# Motorbike_monitoring_and_Alarm.net
KiCad netlist of a schematic drawn in EAGLE
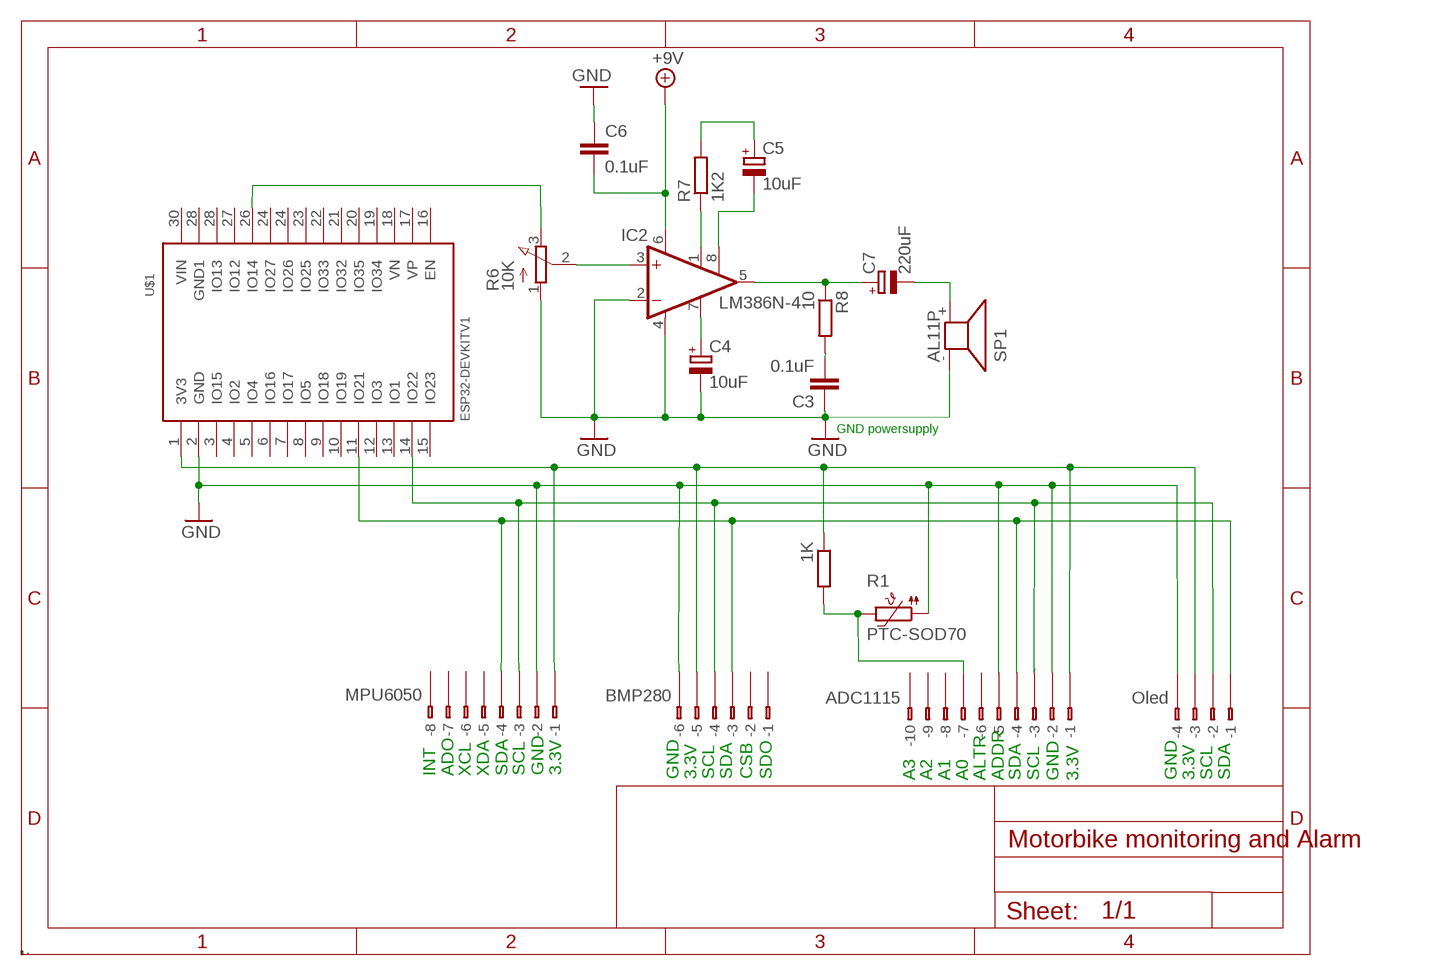
[diagram p0: schematic, sheet 1]

(export (version "E")
  (design (tool "Eeschema 10.0.6"))
  (components
    (comp (ref "ADC1115")
      (value "233-110")
      (footprint "eagle-import:233-110")
      (libsource (lib "eagle-import") (part "233-110"))
    )
    (comp (ref "C3")
      (value "0.1uF")
      (footprint "eagle-import:C050-024X044")
      (libsource (lib "eagle-import") (part "C-EU050-024X044"))
    )
    (comp (ref "C4")
      (value "10uF")
      (footprint "eagle-import:E1,8-4")
      (libsource (lib "eagle-import") (part "CPOL-EUE1.8-4"))
    )
    (comp (ref "C5")
      (value "10uF")
      (footprint "eagle-import:E1,8-4")
      (libsource (lib "eagle-import") (part "CPOL-EUE1.8-4"))
    )
    (comp (ref "C6")
      (value "0.1uF")
      (footprint "eagle-import:C050-024X044")
      (libsource (lib "eagle-import") (part "C-EU050-024X044"))
    )
    (comp (ref "C7")
      (value "220uF")
      (footprint "eagle-import:E1,8-4")
      (libsource (lib "eagle-import") (part "CPOL-EUE1.8-4"))
    )
    (comp (ref "IC2")
      (value "LM386N-4")
      (footprint "eagle-import:DIL08")
      (libsource (lib "eagle-import") (part "LM386?-N4"))
    )
    (comp (ref "MPU6050")
      (value "233-108")
      (footprint "eagle-import:233-108")
      (libsource (lib "eagle-import") (part "233-108"))
    )
    (comp (ref "R1")
      (value "PTC-SOD70")
      (footprint "eagle-import:SOD70")
      (libsource (lib "eagle-import") (part "PTC-SOD70"))
    )
    (comp (ref "R2")
      (value "1K")
      (footprint "eagle-import:0207_7")
      (libsource (lib "eagle-import") (part "R-EU_0207/7"))
    )
    (comp (ref "R6")
      (value "10K")
      (footprint "eagle-import:3RP_1610N")
      (libsource (lib "eagle-import") (part "3RP/1610N"))
    )
    (comp (ref "R7")
      (value "1K2")
      (footprint "eagle-import:0207_7")
      (libsource (lib "eagle-import") (part "R-EU_0207/7"))
    )
    (comp (ref "R8")
      (value "10")
      (footprint "eagle-import:0207_7")
      (libsource (lib "eagle-import") (part "R-EU_0207/7"))
    )
    (comp (ref "SP1")
      (value "AL11P")
      (footprint "eagle-import:AL11P")
      (libsource (lib "eagle-import") (part "AL11P"))
    )
    (comp (ref "U$1")
      (value "ESP32DEVKITV1")
      (footprint "eagle-import:ESP32-DEVKITV1")
      (libsource (lib "eagle-import") (part "ESP32DEVKITV1"))
    )
    (comp (ref "X1")
      (value "Oled")
      (footprint "eagle-import:233-104")
      (fields (field (name "MPN") "233-104"))
      (libsource (lib "eagle-import") (part "233-104"))
    )
    (comp (ref "X5")
      (value "BMP280")
      (footprint "eagle-import:233-106")
      (fields (field (name "MPN") "233-106"))
      (libsource (lib "eagle-import") (part "233-106"))
    )
  )
  (nets
    (net (code "1") (name "+9V") (class "Default")
      (node (ref "C6") (pin "2") (pinfunction "2_2") (pintype "passive"))
      (node (ref "IC2") (pin "6") (pinfunction "VS_6") (pintype "power_in"))
    )
    (net (code "2") (name "GND") (class "Default")
      (node (ref "ADC1115") (pin "B2") (pinfunction "B-2_B2") (pintype "passive"))
      (node (ref "MPU6050") (pin "B2") (pinfunction "B-2_B2") (pintype "passive"))
      (node (ref "U$1") (pin "2") (pinfunction "GND_2") (pintype "bidirectional"))
      (node (ref "X1") (pin "B4") (pinfunction "B-4_B4") (pintype "passive"))
      (node (ref "X5") (pin "B6") (pinfunction "B-6_B6") (pintype "passive"))
    )
    (net (code "3") (name "Net-(ADC1115-B-1)") (class "Default")
      (node (ref "ADC1115") (pin "B1") (pinfunction "B-1_B1") (pintype "passive"))
      (node (ref "MPU6050") (pin "B1") (pinfunction "B-1_B1") (pintype "passive"))
      (node (ref "R2") (pin "1") (pinfunction "1_1") (pintype "passive"))
      (node (ref "U$1") (pin "1") (pinfunction "3V3_1") (pintype "bidirectional"))
      (node (ref "X1") (pin "B3") (pinfunction "B-3_B3") (pintype "passive"))
      (node (ref "X5") (pin "B5") (pinfunction "B-5_B5") (pintype "passive"))
    )
    (net (code "4") (name "Net-(ADC1115-B-3)") (class "Default")
      (node (ref "ADC1115") (pin "B3") (pinfunction "B-3_B3") (pintype "passive"))
      (node (ref "MPU6050") (pin "B3") (pinfunction "B-3_B3") (pintype "passive"))
      (node (ref "U$1") (pin "14") (pinfunction "IO22_14") (pintype "bidirectional"))
      (node (ref "X1") (pin "B2") (pinfunction "B-2_B2") (pintype "passive"))
      (node (ref "X5") (pin "B4") (pinfunction "B-4_B4") (pintype "passive"))
    )
    (net (code "5") (name "Net-(ADC1115-B-4)") (class "Default")
      (node (ref "ADC1115") (pin "B4") (pinfunction "B-4_B4") (pintype "passive"))
      (node (ref "MPU6050") (pin "B4") (pinfunction "B-4_B4") (pintype "passive"))
      (node (ref "U$1") (pin "11") (pinfunction "IO21_11") (pintype "bidirectional"))
      (node (ref "X1") (pin "B1") (pinfunction "B-1_B1") (pintype "passive"))
      (node (ref "X5") (pin "B3") (pinfunction "B-3_B3") (pintype "passive"))
    )
    (net (code "6") (name "Net-(ADC1115-B-7)") (class "Default")
      (node (ref "ADC1115") (pin "B7") (pinfunction "B-7_B7") (pintype "passive"))
      (node (ref "R1") (pin "2") (pinfunction "2_2") (pintype "passive"))
      (node (ref "R2") (pin "2") (pinfunction "2_2") (pintype "passive"))
    )
    (net (code "7") (name "Net-(C3-Pad2)") (class "Default")
      (node (ref "C3") (pin "2") (pinfunction "2_2") (pintype "passive"))
      (node (ref "R8") (pin "2") (pinfunction "2_2") (pintype "passive"))
    )
    (net (code "8") (name "Net-(C5-Pad+)") (class "Default")
      (node (ref "C5") (pin "+") (pinfunction "+_+") (pintype "passive"))
      (node (ref "R7") (pin "2") (pinfunction "2_2") (pintype "passive"))
    )
    (net (code "9") (name "Net-(C5-Pad-)") (class "Default")
      (node (ref "C5") (pin "-") (pinfunction "-_-") (pintype "passive"))
      (node (ref "IC2") (pin "8") (pinfunction "GAIN_8") (pintype "passive"))
    )
    (net (code "10") (name "Net-(IC2-+IN)") (class "Default")
      (node (ref "IC2") (pin "3") (pinfunction "+IN_3") (pintype "input"))
      (node (ref "R6") (pin "2") (pinfunction "S_2") (pintype "passive"))
    )
    (net (code "11") (name "Net-(IC2--IN)") (class "Default")
      (node (ref "C3") (pin "1") (pinfunction "1_1") (pintype "passive"))
      (node (ref "C4") (pin "-") (pinfunction "-_-") (pintype "passive"))
      (node (ref "IC2") (pin "2") (pinfunction "-IN_2") (pintype "input"))
      (node (ref "IC2") (pin "4") (pinfunction "GND_4") (pintype "power_in"))
      (node (ref "R6") (pin "1") (pinfunction "A_1") (pintype "passive"))
      (node (ref "SP1") (pin "-") (pinfunction "1_-") (pintype "passive"))
    )
    (net (code "12") (name "Net-(IC2-BYPASS)") (class "Default")
      (node (ref "C4") (pin "+") (pinfunction "+_+") (pintype "passive"))
      (node (ref "IC2") (pin "7") (pinfunction "BYPASS_7") (pintype "passive"))
    )
    (net (code "13") (name "Net-(IC2-GAIN-Pad1)") (class "Default")
      (node (ref "IC2") (pin "1") (pinfunction "GAIN_1") (pintype "passive"))
      (node (ref "R7") (pin "1") (pinfunction "1_1") (pintype "passive"))
    )
    (net (code "14") (name "Net-(IC2-OUT)") (class "Default")
      (node (ref "C7") (pin "+") (pinfunction "+_+") (pintype "passive"))
      (node (ref "IC2") (pin "5") (pinfunction "OUT_5") (pintype "output"))
      (node (ref "R8") (pin "1") (pinfunction "1_1") (pintype "passive"))
    )
    (net (code "15") (name "Net-(R6-E)") (class "Default")
      (node (ref "R6") (pin "3") (pinfunction "E_3") (pintype "passive"))
      (node (ref "U$1") (pin "26") (pinfunction "IO14_26") (pintype "bidirectional"))
    )
    (net (code "16") (name "Net-(SP1-2)") (class "Default")
      (node (ref "C7") (pin "-") (pinfunction "-_-") (pintype "passive"))
      (node (ref "SP1") (pin "+") (pinfunction "2_+") (pintype "passive"))
    )
    (net (code "17") (name "unconnected-(ADC1115--1-PadA1)") (class "Default")
      (node (ref "ADC1115") (pin "A1") (pinfunction "-1_A1") (pintype "passive"))
    )
    (net (code "18") (name "unconnected-(ADC1115--2-PadA2)") (class "Default")
      (node (ref "ADC1115") (pin "A2") (pinfunction "-2_A2") (pintype "passive"))
    )
    (net (code "19") (name "unconnected-(ADC1115--3-PadA3)") (class "Default")
      (node (ref "ADC1115") (pin "A3") (pinfunction "-3_A3") (pintype "passive"))
    )
    (net (code "20") (name "unconnected-(ADC1115--4-PadA4)") (class "Default")
      (node (ref "ADC1115") (pin "A4") (pinfunction "-4_A4") (pintype "passive"))
    )
    (net (code "21") (name "unconnected-(ADC1115--5-PadA5)") (class "Default")
      (node (ref "ADC1115") (pin "A5") (pinfunction "-5_A5") (pintype "passive"))
    )
    (net (code "22") (name "unconnected-(ADC1115--6-PadA6)") (class "Default")
      (node (ref "ADC1115") (pin "A6") (pinfunction "-6_A6") (pintype "passive"))
    )
    (net (code "23") (name "unconnected-(ADC1115--7-PadA7)") (class "Default")
      (node (ref "ADC1115") (pin "A7") (pinfunction "-7_A7") (pintype "passive"))
    )
    (net (code "24") (name "unconnected-(ADC1115--8-PadA8)") (class "Default")
      (node (ref "ADC1115") (pin "A8") (pinfunction "-8_A8") (pintype "passive"))
    )
    (net (code "25") (name "unconnected-(ADC1115--9-PadA9)") (class "Default")
      (node (ref "ADC1115") (pin "A9") (pinfunction "-9_A9") (pintype "passive"))
    )
    (net (code "26") (name "unconnected-(ADC1115--10-PadA10)") (class "Default")
      (node (ref "ADC1115") (pin "A10") (pinfunction "-10_A10") (pintype "passive"))
    )
    (net (code "27") (name "unconnected-(ADC1115-B-5-PadB5)") (class "Default")
      (node (ref "ADC1115") (pin "B5") (pinfunction "B-5_B5") (pintype "passive"))
    )
    (net (code "28") (name "unconnected-(ADC1115-B-6-PadB6)") (class "Default")
      (node (ref "ADC1115") (pin "B6") (pinfunction "B-6_B6") (pintype "passive"))
    )
    (net (code "29") (name "unconnected-(ADC1115-B-8-PadB8)") (class "Default")
      (node (ref "ADC1115") (pin "B8") (pinfunction "B-8_B8") (pintype "passive"))
    )
    (net (code "30") (name "unconnected-(ADC1115-B-9-PadB9)") (class "Default")
      (node (ref "ADC1115") (pin "B9") (pinfunction "B-9_B9") (pintype "passive"))
    )
    (net (code "31") (name "unconnected-(ADC1115-B-10-PadB10)") (class "Default")
      (node (ref "ADC1115") (pin "B10") (pinfunction "B-10_B10") (pintype "passive"))
    )
    (net (code "32") (name "unconnected-(C6-Pad1)") (class "Default")
      (node (ref "C6") (pin "1") (pinfunction "1_1") (pintype "passive"))
    )
    (net (code "33") (name "unconnected-(MPU6050--1-PadA1)") (class "Default")
      (node (ref "MPU6050") (pin "A1") (pinfunction "-1_A1") (pintype "passive"))
    )
    (net (code "34") (name "unconnected-(MPU6050--2-PadA2)") (class "Default")
      (node (ref "MPU6050") (pin "A2") (pinfunction "-2_A2") (pintype "passive"))
    )
    (net (code "35") (name "unconnected-(MPU6050--3-PadA3)") (class "Default")
      (node (ref "MPU6050") (pin "A3") (pinfunction "-3_A3") (pintype "passive"))
    )
    (net (code "36") (name "unconnected-(MPU6050--4-PadA4)") (class "Default")
      (node (ref "MPU6050") (pin "A4") (pinfunction "-4_A4") (pintype "passive"))
    )
    (net (code "37") (name "unconnected-(MPU6050--5-PadA5)") (class "Default")
      (node (ref "MPU6050") (pin "A5") (pinfunction "-5_A5") (pintype "passive"))
    )
    (net (code "38") (name "unconnected-(MPU6050--6-PadA6)") (class "Default")
      (node (ref "MPU6050") (pin "A6") (pinfunction "-6_A6") (pintype "passive"))
    )
    (net (code "39") (name "unconnected-(MPU6050--7-PadA7)") (class "Default")
      (node (ref "MPU6050") (pin "A7") (pinfunction "-7_A7") (pintype "passive"))
    )
    (net (code "40") (name "unconnected-(MPU6050--8-PadA8)") (class "Default")
      (node (ref "MPU6050") (pin "A8") (pinfunction "-8_A8") (pintype "passive"))
    )
    (net (code "41") (name "unconnected-(MPU6050-B-5-PadB5)") (class "Default")
      (node (ref "MPU6050") (pin "B5") (pinfunction "B-5_B5") (pintype "passive"))
    )
    (net (code "42") (name "unconnected-(MPU6050-B-6-PadB6)") (class "Default")
      (node (ref "MPU6050") (pin "B6") (pinfunction "B-6_B6") (pintype "passive"))
    )
    (net (code "43") (name "unconnected-(MPU6050-B-7-PadB7)") (class "Default")
      (node (ref "MPU6050") (pin "B7") (pinfunction "B-7_B7") (pintype "passive"))
    )
    (net (code "44") (name "unconnected-(MPU6050-B-8-PadB8)") (class "Default")
      (node (ref "MPU6050") (pin "B8") (pinfunction "B-8_B8") (pintype "passive"))
    )
    (net (code "45") (name "unconnected-(R1-Pad1)") (class "Default")
      (node (ref "R1") (pin "1") (pinfunction "1_1") (pintype "passive"))
    )
    (net (code "46") (name "unconnected-(U$1-EN-Pad16)") (class "Default")
      (node (ref "U$1") (pin "16") (pinfunction "EN_16") (pintype "bidirectional"))
    )
    (net (code "47") (name "unconnected-(U$1-GND1-Pad28)") (class "Default")
      (node (ref "U$1") (pin "28") (pinfunction "GND1_28") (pintype "bidirectional"))
    )
    (net (code "48") (name "unconnected-(U$1-IO1-Pad13)") (class "Default")
      (node (ref "U$1") (pin "13") (pinfunction "IO1_13") (pintype "bidirectional"))
    )
    (net (code "49") (name "unconnected-(U$1-IO2-Pad4)") (class "Default")
      (node (ref "U$1") (pin "4") (pinfunction "IO2_4") (pintype "bidirectional"))
    )
    (net (code "50") (name "unconnected-(U$1-IO3-Pad12)") (class "Default")
      (node (ref "U$1") (pin "12") (pinfunction "IO3_12") (pintype "bidirectional"))
    )
    (net (code "51") (name "unconnected-(U$1-IO4-Pad5)") (class "Default")
      (node (ref "U$1") (pin "5") (pinfunction "IO4_5") (pintype "bidirectional"))
    )
    (net (code "52") (name "unconnected-(U$1-IO5-Pad8)") (class "Default")
      (node (ref "U$1") (pin "8") (pinfunction "IO5_8") (pintype "bidirectional"))
    )
    (net (code "53") (name "unconnected-(U$1-IO12-Pad27)") (class "Default")
      (node (ref "U$1") (pin "27") (pinfunction "IO12_27") (pintype "bidirectional"))
    )
    (net (code "54") (name "unconnected-(U$1-IO13-Pad28)") (class "Default")
      (node (ref "U$1") (pin "28") (pinfunction "IO13_28") (pintype "bidirectional"))
    )
    (net (code "55") (name "unconnected-(U$1-IO15-Pad3)") (class "Default")
      (node (ref "U$1") (pin "3") (pinfunction "IO15_3") (pintype "bidirectional"))
    )
    (net (code "56") (name "unconnected-(U$1-IO16-Pad6)") (class "Default")
      (node (ref "U$1") (pin "6") (pinfunction "IO16_6") (pintype "bidirectional"))
    )
    (net (code "57") (name "unconnected-(U$1-IO17-Pad7)") (class "Default")
      (node (ref "U$1") (pin "7") (pinfunction "IO17_7") (pintype "bidirectional"))
    )
    (net (code "58") (name "unconnected-(U$1-IO18-Pad9)") (class "Default")
      (node (ref "U$1") (pin "9") (pinfunction "IO18_9") (pintype "bidirectional"))
    )
    (net (code "59") (name "unconnected-(U$1-IO19-Pad10)") (class "Default")
      (node (ref "U$1") (pin "10") (pinfunction "IO19_10") (pintype "bidirectional"))
    )
    (net (code "60") (name "unconnected-(U$1-IO23-Pad15)") (class "Default")
      (node (ref "U$1") (pin "15") (pinfunction "IO23_15") (pintype "bidirectional"))
    )
    (net (code "61") (name "unconnected-(U$1-IO25-Pad23)") (class "Default")
      (node (ref "U$1") (pin "23") (pinfunction "IO25_23") (pintype "bidirectional"))
    )
    (net (code "62") (name "unconnected-(U$1-IO26-Pad24)") (class "Default")
      (node (ref "U$1") (pin "24") (pinfunction "IO26_24") (pintype "bidirectional"))
    )
    (net (code "63") (name "unconnected-(U$1-IO27-Pad24)") (class "Default")
      (node (ref "U$1") (pin "24") (pinfunction "IO27_24") (pintype "bidirectional"))
    )
    (net (code "64") (name "unconnected-(U$1-IO32-Pad21)") (class "Default")
      (node (ref "U$1") (pin "21") (pinfunction "IO32_21") (pintype "bidirectional"))
    )
    (net (code "65") (name "unconnected-(U$1-IO33-Pad22)") (class "Default")
      (node (ref "U$1") (pin "22") (pinfunction "IO33_22") (pintype "bidirectional"))
    )
    (net (code "66") (name "unconnected-(U$1-IO34-Pad19)") (class "Default")
      (node (ref "U$1") (pin "19") (pinfunction "IO34_19") (pintype "bidirectional"))
    )
    (net (code "67") (name "unconnected-(U$1-IO35-Pad20)") (class "Default")
      (node (ref "U$1") (pin "20") (pinfunction "IO35_20") (pintype "bidirectional"))
    )
    (net (code "68") (name "unconnected-(U$1-VIN-Pad30)") (class "Default")
      (node (ref "U$1") (pin "30") (pinfunction "VIN_30") (pintype "bidirectional"))
    )
    (net (code "69") (name "unconnected-(U$1-VN-Pad18)") (class "Default")
      (node (ref "U$1") (pin "18") (pinfunction "VN_18") (pintype "bidirectional"))
    )
    (net (code "70") (name "unconnected-(U$1-VP-Pad17)") (class "Default")
      (node (ref "U$1") (pin "17") (pinfunction "VP_17") (pintype "bidirectional"))
    )
    (net (code "71") (name "unconnected-(X1--1-PadA1)") (class "Default")
      (node (ref "X1") (pin "A1") (pinfunction "-1_A1") (pintype "passive"))
    )
    (net (code "72") (name "unconnected-(X1--2-PadA2)") (class "Default")
      (node (ref "X1") (pin "A2") (pinfunction "-2_A2") (pintype "passive"))
    )
    (net (code "73") (name "unconnected-(X1--3-PadA3)") (class "Default")
      (node (ref "X1") (pin "A3") (pinfunction "-3_A3") (pintype "passive"))
    )
    (net (code "74") (name "unconnected-(X1--4-PadA4)") (class "Default")
      (node (ref "X1") (pin "A4") (pinfunction "-4_A4") (pintype "passive"))
    )
    (net (code "75") (name "unconnected-(X5--1-PadA1)") (class "Default")
      (node (ref "X5") (pin "A1") (pinfunction "-1_A1") (pintype "passive"))
    )
    (net (code "76") (name "unconnected-(X5--2-PadA2)") (class "Default")
      (node (ref "X5") (pin "A2") (pinfunction "-2_A2") (pintype "passive"))
    )
    (net (code "77") (name "unconnected-(X5--3-PadA3)") (class "Default")
      (node (ref "X5") (pin "A3") (pinfunction "-3_A3") (pintype "passive"))
    )
    (net (code "78") (name "unconnected-(X5--4-PadA4)") (class "Default")
      (node (ref "X5") (pin "A4") (pinfunction "-4_A4") (pintype "passive"))
    )
    (net (code "79") (name "unconnected-(X5--5-PadA5)") (class "Default")
      (node (ref "X5") (pin "A5") (pinfunction "-5_A5") (pintype "passive"))
    )
    (net (code "80") (name "unconnected-(X5--6-PadA6)") (class "Default")
      (node (ref "X5") (pin "A6") (pinfunction "-6_A6") (pintype "passive"))
    )
    (net (code "81") (name "unconnected-(X5-B-1-PadB1)") (class "Default")
      (node (ref "X5") (pin "B1") (pinfunction "B-1_B1") (pintype "passive"))
    )
    (net (code "82") (name "unconnected-(X5-B-2-PadB2)") (class "Default")
      (node (ref "X5") (pin "B2") (pinfunction "B-2_B2") (pintype "passive"))
    )
  )
)
